# ptschematic.net
KiCad netlist of a schematic drawn in EAGLE
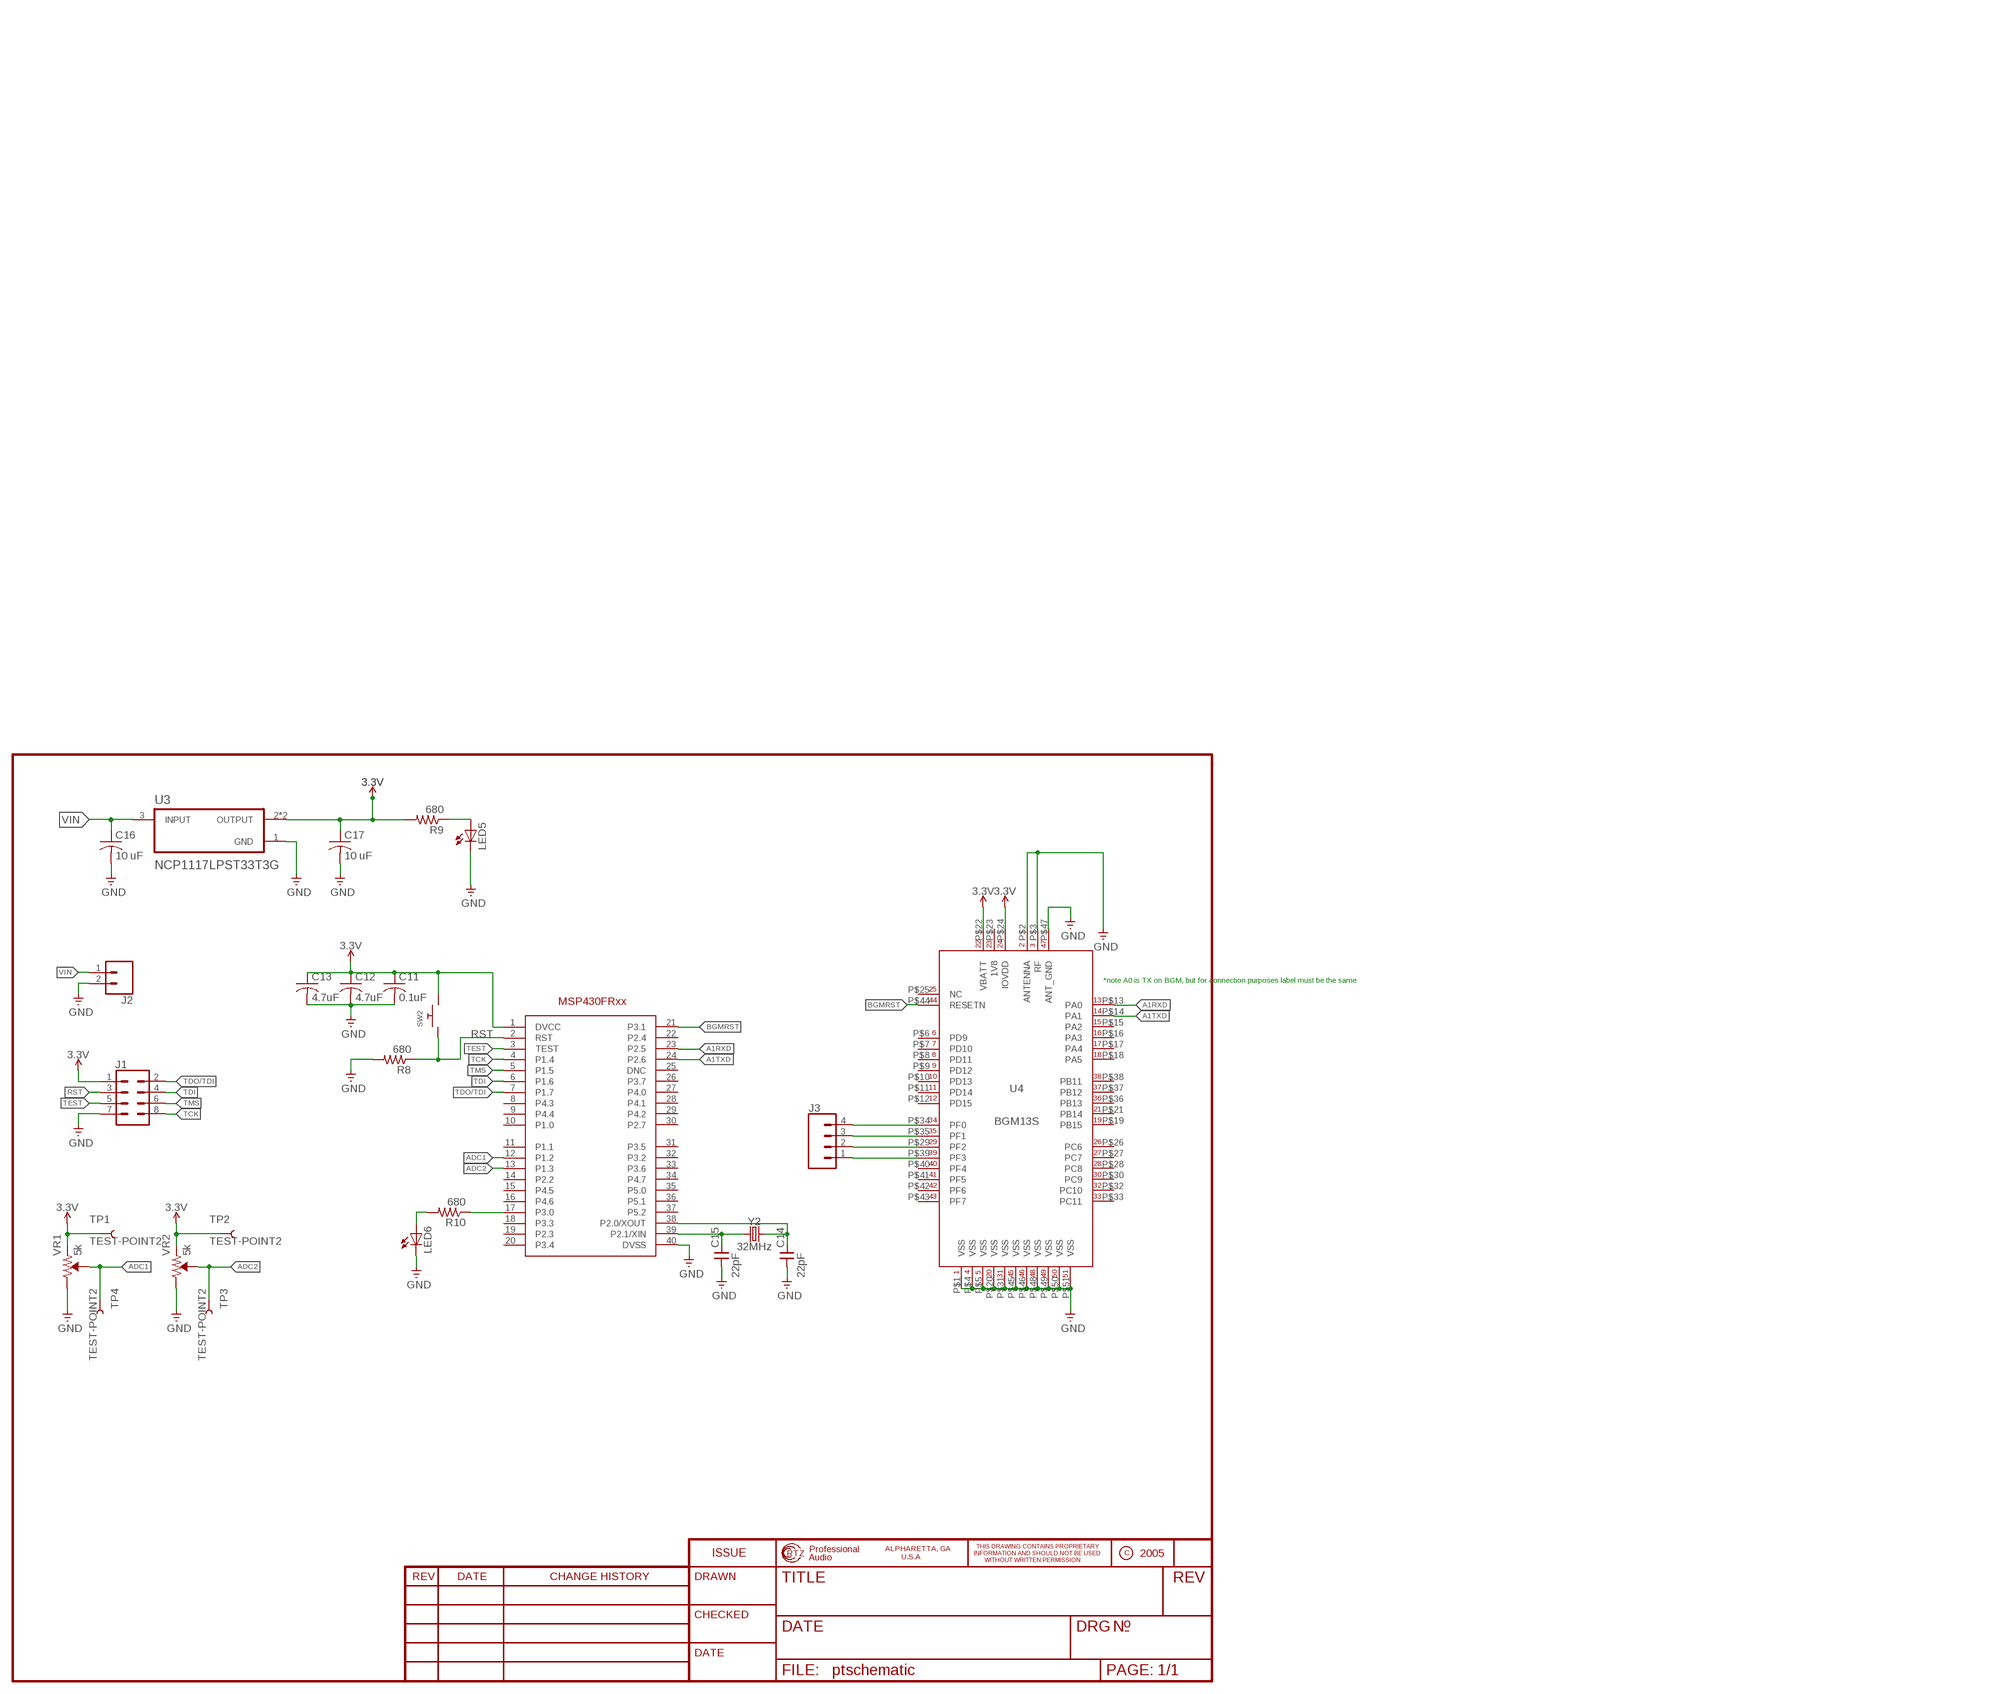
[diagram p0: schematic, sheet 1]

(export (version "E")
  (design (tool "Eeschema 10.0.6"))
  (components
    (comp (ref "C11")
      (value "0.1uF")
      (footprint "eagle-import:C0805")
      (libsource (lib "eagle-import") (part "C-USC0805"))
    )
    (comp (ref "C12")
      (value "4.7uF")
      (footprint "eagle-import:C0805")
      (libsource (lib "eagle-import") (part "C-USC0805"))
    )
    (comp (ref "C13")
      (value "4.7uF")
      (footprint "eagle-import:C0805")
      (libsource (lib "eagle-import") (part "C-USC0805"))
    )
    (comp (ref "C14")
      (value "22pF")
      (footprint "eagle-import:0805")
      (libsource (lib "eagle-import") (part "CNP-0805"))
    )
    (comp (ref "C15")
      (value "22pF")
      (footprint "eagle-import:0805")
      (libsource (lib "eagle-import") (part "CNP-0805"))
    )
    (comp (ref "C16")
      (value "10 uF")
      (footprint "eagle-import:C0805")
      (libsource (lib "eagle-import") (part "C-USC0805"))
    )
    (comp (ref "C17")
      (value "10 uF")
      (footprint "eagle-import:C0805")
      (libsource (lib "eagle-import") (part "C-USC0805"))
    )
    (comp (ref "J1")
      (value "CONN_04X2")
      (footprint "eagle-import:2X4")
      (libsource (lib "eagle-import") (part "CONN_04X2"))
    )
    (comp (ref "J2")
      (value "CONN_02")
      (footprint "eagle-import:1X02")
      (libsource (lib "eagle-import") (part "CONN_02"))
    )
    (comp (ref "J3")
      (value "CONN_04")
      (footprint "eagle-import:1X04")
      (libsource (lib "eagle-import") (part "CONN_04"))
    )
    (comp (ref "LED5")
      (value "LEDCHIPLED_0805")
      (footprint "eagle-import:CHIPLED_0805")
      (libsource (lib "eagle-import") (part "LEDCHIPLED_0805"))
    )
    (comp (ref "LED6")
      (value "LEDCHIPLED_0805")
      (footprint "eagle-import:CHIPLED_0805")
      (libsource (lib "eagle-import") (part "LEDCHIPLED_0805"))
    )
    (comp (ref "R8")
      (value "680")
      (footprint "eagle-import:R0805")
      (libsource (lib "eagle-import") (part "R-US_R0805"))
    )
    (comp (ref "R9")
      (value "680")
      (footprint "eagle-import:R0805")
      (libsource (lib "eagle-import") (part "R-US_R0805"))
    )
    (comp (ref "R10")
      (value "680")
      (footprint "eagle-import:R0805")
      (libsource (lib "eagle-import") (part "R-US_R0805"))
    )
    (comp (ref "SW2")
      (value "SWITCH_PUSHBUTTONEVQ-PE")
      (footprint "eagle-import:TACT_PANA-EVQ")
      (libsource (lib "eagle-import") (part "SWITCH_PUSHBUTTONEVQ-PE"))
    )
    (comp (ref "TP1")
      (value "TEST-POINT2")
      (footprint "eagle-import:PAD.02X.02")
      (libsource (lib "eagle-import") (part "TEST-POINT2"))
    )
    (comp (ref "TP2")
      (value "TEST-POINT2")
      (footprint "eagle-import:PAD.02X.02")
      (libsource (lib "eagle-import") (part "TEST-POINT2"))
    )
    (comp (ref "TP3")
      (value "TEST-POINT2")
      (footprint "eagle-import:PAD.02X.02")
      (libsource (lib "eagle-import") (part "TEST-POINT2"))
    )
    (comp (ref "TP4")
      (value "TEST-POINT2")
      (footprint "eagle-import:PAD.02X.02")
      (libsource (lib "eagle-import") (part "TEST-POINT2"))
    )
    (comp (ref "U$1")
      (value "MSP340FR247")
      (footprint "eagle-import:QFN-40")
      (libsource (lib "eagle-import") (part "MSP340FR247"))
    )
    (comp (ref "U3")
      (value "NCP1117LPST33T3G")
      (footprint "eagle-import:SOT230P700X175-4N")
      (fields (field (name "MF") "ON Semiconductor"))
      (libsource (lib "eagle-import") (part "NCP1117LPST33T3G"))
    )
    (comp (ref "U4")
      (value "BGM13S")
      (footprint "eagle-import:BGM13S")
      (libsource (lib "eagle-import") (part "BGM13S"))
    )
    (comp (ref "VR1")
      (value "5k")
      (footprint "eagle-import:TRIMPOT-SMD-5MM")
      (libsource (lib "eagle-import") (part "TRIMPOT-SMD-5MM-CLOSED-1/4W-20%"))
    )
    (comp (ref "VR2")
      (value "5k")
      (footprint "eagle-import:TRIMPOT-SMD-5MM")
      (libsource (lib "eagle-import") (part "TRIMPOT-SMD-5MM-CLOSED-1/4W-20%"))
    )
    (comp (ref "Y2")
      (value "32MHz")
      (footprint "eagle-import:CRYSTAL-SMD-2.0X1.6MM")
      (libsource (lib "eagle-import") (part "CRYSTAL-32MHZ-SMD-2.0X1.6MM"))
    )
  )
  (nets
    (net (code "1") (name "/1V8") (class "Default")
      (node (ref "U4") (pin "P$23") (pinfunction "1V8_P$23") (pintype "power_in"))
    )
    (net (code "2") (name "3.3V") (class "Default")
      (node (ref "C11") (pin "1") (pinfunction "1_1") (pintype "passive"))
      (node (ref "C12") (pin "1") (pinfunction "1_1") (pintype "passive"))
      (node (ref "C13") (pin "1") (pinfunction "1_1") (pintype "passive"))
      (node (ref "C17") (pin "1") (pinfunction "1_1") (pintype "passive"))
      (node (ref "J1") (pin "1") (pinfunction "1_1") (pintype "passive"))
      (node (ref "R9") (pin "2") (pinfunction "2_2") (pintype "passive"))
      (node (ref "SW2") (pin "P$2") (pinfunction "P$2_P$2") (pintype "passive"))
      (node (ref "TP1") (pin "P$1") (pinfunction "1_P$1") (pintype "bidirectional"))
      (node (ref "TP2") (pin "P$1") (pinfunction "1_P$1") (pintype "bidirectional"))
      (node (ref "U$1") (pin "1") (pinfunction "DVCC_1") (pintype "bidirectional"))
      (node (ref "U3") (pin "2") (pinfunction "OUTPUT_2") (pintype "output"))
      (node (ref "U3") (pin "4") (pinfunction "OUTPUT_4") (pintype "output"))
      (node (ref "U4") (pin "P$22") (pinfunction "VBATT_P$22") (pintype "power_in"))
      (node (ref "U4") (pin "P$24") (pinfunction "IOVDD_P$24") (pintype "power_in"))
      (node (ref "VR1") (pin "A") (pinfunction "CCW_A") (pintype "passive"))
      (node (ref "VR2") (pin "A") (pinfunction "CCW_A") (pintype "passive"))
    )
    (net (code "3") (name "A1RXD") (class "Default")
      (node (ref "U$1") (pin "23") (pinfunction "P2.5_23") (pintype "bidirectional"))
      (node (ref "U4") (pin "P$13") (pinfunction "PA0_P$13") (pintype "bidirectional"))
    )
    (net (code "4") (name "A1TXD") (class "Default")
      (node (ref "U$1") (pin "24") (pinfunction "P2.6_24") (pintype "bidirectional"))
      (node (ref "U4") (pin "P$14") (pinfunction "PA1_P$14") (pintype "bidirectional"))
    )
    (net (code "5") (name "ADC1") (class "Default")
      (node (ref "TP4") (pin "P$1") (pinfunction "1_P$1") (pintype "bidirectional"))
      (node (ref "U$1") (pin "12") (pinfunction "P1.2_12") (pintype "bidirectional"))
      (node (ref "VR1") (pin "B") (pinfunction "WIPER_B") (pintype "passive"))
    )
    (net (code "6") (name "ADC2") (class "Default")
      (node (ref "TP3") (pin "P$1") (pinfunction "1_P$1") (pintype "bidirectional"))
      (node (ref "U$1") (pin "13") (pinfunction "P1.3_13") (pintype "bidirectional"))
      (node (ref "VR2") (pin "B") (pinfunction "WIPER_B") (pintype "passive"))
    )
    (net (code "7") (name "BGMRST") (class "Default")
      (node (ref "U$1") (pin "21") (pinfunction "P3.1_21") (pintype "bidirectional"))
      (node (ref "U4") (pin "P$44") (pinfunction "RESETN_P$44") (pintype "bidirectional"))
    )
    (net (code "8") (name "GND") (class "Default")
      (node (ref "C11") (pin "2") (pinfunction "2_2") (pintype "passive"))
      (node (ref "C12") (pin "2") (pinfunction "2_2") (pintype "passive"))
      (node (ref "C13") (pin "2") (pinfunction "2_2") (pintype "passive"))
      (node (ref "C14") (pin "1") (pinfunction "1_1") (pintype "passive"))
      (node (ref "C15") (pin "1") (pinfunction "1_1") (pintype "passive"))
      (node (ref "C16") (pin "2") (pinfunction "2_2") (pintype "passive"))
      (node (ref "C17") (pin "2") (pinfunction "2_2") (pintype "passive"))
      (node (ref "J1") (pin "7") (pinfunction "7_7") (pintype "passive"))
      (node (ref "J2") (pin "2") (pinfunction "2_2") (pintype "passive"))
      (node (ref "LED5") (pin "C") (pinfunction "C_C") (pintype "passive"))
      (node (ref "LED6") (pin "C") (pinfunction "C_C") (pintype "passive"))
      (node (ref "R8") (pin "2") (pinfunction "2_2") (pintype "passive"))
      (node (ref "U$1") (pin "40") (pinfunction "DVSS_40") (pintype "bidirectional"))
      (node (ref "U3") (pin "1") (pinfunction "GND_1") (pintype "power_in"))
      (node (ref "U4") (pin "P$1") (pinfunction "VSS_P$1") (pintype "power_in"))
      (node (ref "U4") (pin "P$2") (pinfunction "ANTENNA_P$2") (pintype "passive"))
      (node (ref "U4") (pin "P$20") (pinfunction "VSS_P$20") (pintype "power_in"))
      (node (ref "U4") (pin "P$3") (pinfunction "RF_P$3") (pintype "passive"))
      (node (ref "U4") (pin "P$31") (pinfunction "VSS_P$31") (pintype "power_in"))
      (node (ref "U4") (pin "P$4") (pinfunction "VSS_P$4") (pintype "power_in"))
      (node (ref "U4") (pin "P$45") (pinfunction "VSS_P$45") (pintype "power_in"))
      (node (ref "U4") (pin "P$46") (pinfunction "VSS_P$46") (pintype "power_in"))
      (node (ref "U4") (pin "P$47") (pinfunction "ANT_GND_P$47") (pintype "power_in"))
      (node (ref "U4") (pin "P$48") (pinfunction "VSS_P$48") (pintype "power_in"))
      (node (ref "U4") (pin "P$49") (pinfunction "VSS_P$49") (pintype "power_in"))
      (node (ref "U4") (pin "P$5") (pinfunction "VSS_P$5") (pintype "power_in"))
      (node (ref "U4") (pin "P$50") (pinfunction "VSS_P$50") (pintype "power_in"))
      (node (ref "U4") (pin "P$51") (pinfunction "VSS_P$51") (pintype "power_in"))
      (node (ref "VR1") (pin "C") (pinfunction "CW_C") (pintype "passive"))
      (node (ref "VR2") (pin "C") (pinfunction "CW_C") (pintype "passive"))
    )
    (net (code "9") (name "Net-(LED5-PadA)") (class "Default")
      (node (ref "LED5") (pin "A") (pinfunction "A_A") (pintype "passive"))
      (node (ref "R9") (pin "1") (pinfunction "1_1") (pintype "passive"))
    )
    (net (code "10") (name "Net-(LED6-PadA)") (class "Default")
      (node (ref "LED6") (pin "A") (pinfunction "A_A") (pintype "passive"))
      (node (ref "R10") (pin "2") (pinfunction "2_2") (pintype "passive"))
    )
    (net (code "11") (name "Net-(U$1-P2.0{slash}XOUT)") (class "Default")
      (node (ref "C14") (pin "2") (pinfunction "2_2") (pintype "passive"))
      (node (ref "U$1") (pin "38") (pinfunction "P2.0/XOUT_38") (pintype "bidirectional"))
      (node (ref "Y2") (pin "3") (pinfunction "2_3") (pintype "passive"))
    )
    (net (code "12") (name "Net-(U$1-P2.1{slash}XIN)") (class "Default")
      (node (ref "C15") (pin "2") (pinfunction "2_2") (pintype "passive"))
      (node (ref "U$1") (pin "39") (pinfunction "P2.1/XIN_39") (pintype "bidirectional"))
      (node (ref "Y2") (pin "1") (pinfunction "1_1") (pintype "passive"))
    )
    (net (code "13") (name "Net-(U$1-P3.0)") (class "Default")
      (node (ref "R10") (pin "1") (pinfunction "1_1") (pintype "passive"))
      (node (ref "U$1") (pin "17") (pinfunction "P3.0_17") (pintype "bidirectional"))
    )
    (net (code "14") (name "Net-(U4-PF0)") (class "Default")
      (node (ref "J3") (pin "4") (pinfunction "4_4") (pintype "passive"))
      (node (ref "U4") (pin "P$34") (pinfunction "PF0_P$34") (pintype "bidirectional"))
    )
    (net (code "15") (name "Net-(U4-PF1)") (class "Default")
      (node (ref "J3") (pin "3") (pinfunction "3_3") (pintype "passive"))
      (node (ref "U4") (pin "P$35") (pinfunction "PF1_P$35") (pintype "bidirectional"))
    )
    (net (code "16") (name "Net-(U4-PF2)") (class "Default")
      (node (ref "J3") (pin "2") (pinfunction "2_2") (pintype "passive"))
      (node (ref "U4") (pin "P$29") (pinfunction "PF2_P$29") (pintype "bidirectional"))
    )
    (net (code "17") (name "Net-(U4-PF3)") (class "Default")
      (node (ref "J3") (pin "1") (pinfunction "1_1") (pintype "passive"))
      (node (ref "U4") (pin "P$39") (pinfunction "PF3_P$39") (pintype "bidirectional"))
    )
    (net (code "18") (name "RST") (class "Default")
      (node (ref "J1") (pin "3") (pinfunction "3_3") (pintype "passive"))
      (node (ref "R8") (pin "1") (pinfunction "1_1") (pintype "passive"))
      (node (ref "SW2") (pin "P$1") (pinfunction "P$1_P$1") (pintype "passive"))
      (node (ref "U$1") (pin "2") (pinfunction "RST_2") (pintype "bidirectional"))
    )
    (net (code "19") (name "TCK") (class "Default")
      (node (ref "J1") (pin "8") (pinfunction "8_8") (pintype "passive"))
      (node (ref "U$1") (pin "4") (pinfunction "P1.4_4") (pintype "bidirectional"))
    )
    (net (code "20") (name "TDI") (class "Default")
      (node (ref "J1") (pin "4") (pinfunction "4_4") (pintype "passive"))
      (node (ref "U$1") (pin "6") (pinfunction "P1.6_6") (pintype "bidirectional"))
    )
    (net (code "21") (name "TDO{slash}TDI") (class "Default")
      (node (ref "J1") (pin "2") (pinfunction "2_2") (pintype "passive"))
      (node (ref "U$1") (pin "7") (pinfunction "P1.7_7") (pintype "bidirectional"))
    )
    (net (code "22") (name "TEST") (class "Default")
      (node (ref "J1") (pin "5") (pinfunction "5_5") (pintype "passive"))
      (node (ref "U$1") (pin "3") (pinfunction "TEST_3") (pintype "bidirectional"))
    )
    (net (code "23") (name "TMS") (class "Default")
      (node (ref "J1") (pin "6") (pinfunction "6_6") (pintype "passive"))
      (node (ref "U$1") (pin "5") (pinfunction "P1.5_5") (pintype "bidirectional"))
    )
    (net (code "24") (name "VIN") (class "Default")
      (node (ref "C16") (pin "1") (pinfunction "1_1") (pintype "passive"))
      (node (ref "J2") (pin "1") (pinfunction "1_1") (pintype "passive"))
      (node (ref "U3") (pin "3") (pinfunction "INPUT_3") (pintype "input"))
    )
    (net (code "25") (name "unconnected-(U$1-DNC-Pad25)") (class "Default")
      (node (ref "U$1") (pin "25") (pinfunction "DNC_25") (pintype "bidirectional"))
    )
    (net (code "26") (name "unconnected-(U$1-P1.0-Pad10)") (class "Default")
      (node (ref "U$1") (pin "10") (pinfunction "P1.0_10") (pintype "bidirectional"))
    )
    (net (code "27") (name "unconnected-(U$1-P1.1-Pad11)") (class "Default")
      (node (ref "U$1") (pin "11") (pinfunction "P1.1_11") (pintype "bidirectional"))
    )
    (net (code "28") (name "unconnected-(U$1-P2.2-Pad14)") (class "Default")
      (node (ref "U$1") (pin "14") (pinfunction "P2.2_14") (pintype "bidirectional"))
    )
    (net (code "29") (name "unconnected-(U$1-P2.3-Pad19)") (class "Default")
      (node (ref "U$1") (pin "19") (pinfunction "P2.3_19") (pintype "bidirectional"))
    )
    (net (code "30") (name "unconnected-(U$1-P2.4-Pad22)") (class "Default")
      (node (ref "U$1") (pin "22") (pinfunction "P2.4_22") (pintype "bidirectional"))
    )
    (net (code "31") (name "unconnected-(U$1-P2.7-Pad30)") (class "Default")
      (node (ref "U$1") (pin "30") (pinfunction "P2.7_30") (pintype "bidirectional"))
    )
    (net (code "32") (name "unconnected-(U$1-P3.2-Pad32)") (class "Default")
      (node (ref "U$1") (pin "32") (pinfunction "P3.2_32") (pintype "bidirectional"))
    )
    (net (code "33") (name "unconnected-(U$1-P3.3-Pad18)") (class "Default")
      (node (ref "U$1") (pin "18") (pinfunction "P3.3_18") (pintype "bidirectional"))
    )
    (net (code "34") (name "unconnected-(U$1-P3.4-Pad20)") (class "Default")
      (node (ref "U$1") (pin "20") (pinfunction "P3.4_20") (pintype "bidirectional"))
    )
    (net (code "35") (name "unconnected-(U$1-P3.5-Pad31)") (class "Default")
      (node (ref "U$1") (pin "31") (pinfunction "P3.5_31") (pintype "bidirectional"))
    )
    (net (code "36") (name "unconnected-(U$1-P3.6-Pad33)") (class "Default")
      (node (ref "U$1") (pin "33") (pinfunction "P3.6_33") (pintype "bidirectional"))
    )
    (net (code "37") (name "unconnected-(U$1-P3.7-Pad26)") (class "Default")
      (node (ref "U$1") (pin "26") (pinfunction "P3.7_26") (pintype "bidirectional"))
    )
    (net (code "38") (name "unconnected-(U$1-P4.0-Pad27)") (class "Default")
      (node (ref "U$1") (pin "27") (pinfunction "P4.0_27") (pintype "bidirectional"))
    )
    (net (code "39") (name "unconnected-(U$1-P4.1-Pad28)") (class "Default")
      (node (ref "U$1") (pin "28") (pinfunction "P4.1_28") (pintype "bidirectional"))
    )
    (net (code "40") (name "unconnected-(U$1-P4.2-Pad29)") (class "Default")
      (node (ref "U$1") (pin "29") (pinfunction "P4.2_29") (pintype "bidirectional"))
    )
    (net (code "41") (name "unconnected-(U$1-P4.3-Pad8)") (class "Default")
      (node (ref "U$1") (pin "8") (pinfunction "P4.3_8") (pintype "bidirectional"))
    )
    (net (code "42") (name "unconnected-(U$1-P4.4-Pad9)") (class "Default")
      (node (ref "U$1") (pin "9") (pinfunction "P4.4_9") (pintype "bidirectional"))
    )
    (net (code "43") (name "unconnected-(U$1-P4.5-Pad15)") (class "Default")
      (node (ref "U$1") (pin "15") (pinfunction "P4.5_15") (pintype "bidirectional"))
    )
    (net (code "44") (name "unconnected-(U$1-P4.6-Pad16)") (class "Default")
      (node (ref "U$1") (pin "16") (pinfunction "P4.6_16") (pintype "bidirectional"))
    )
    (net (code "45") (name "unconnected-(U$1-P4.7-Pad34)") (class "Default")
      (node (ref "U$1") (pin "34") (pinfunction "P4.7_34") (pintype "bidirectional"))
    )
    (net (code "46") (name "unconnected-(U$1-P5.0-Pad35)") (class "Default")
      (node (ref "U$1") (pin "35") (pinfunction "P5.0_35") (pintype "bidirectional"))
    )
    (net (code "47") (name "unconnected-(U$1-P5.1-Pad36)") (class "Default")
      (node (ref "U$1") (pin "36") (pinfunction "P5.1_36") (pintype "bidirectional"))
    )
    (net (code "48") (name "unconnected-(U$1-P5.2-Pad37)") (class "Default")
      (node (ref "U$1") (pin "37") (pinfunction "P5.2_37") (pintype "bidirectional"))
    )
    (net (code "49") (name "unconnected-(U4-NC-PadP$25)") (class "Default")
      (node (ref "U4") (pin "P$25") (pinfunction "NC_P$25") (pintype "no_connect"))
    )
    (net (code "50") (name "unconnected-(U4-PA2-PadP$15)") (class "Default")
      (node (ref "U4") (pin "P$15") (pinfunction "PA2_P$15") (pintype "bidirectional"))
    )
    (net (code "51") (name "unconnected-(U4-PA3-PadP$16)") (class "Default")
      (node (ref "U4") (pin "P$16") (pinfunction "PA3_P$16") (pintype "bidirectional"))
    )
    (net (code "52") (name "unconnected-(U4-PA4-PadP$17)") (class "Default")
      (node (ref "U4") (pin "P$17") (pinfunction "PA4_P$17") (pintype "bidirectional"))
    )
    (net (code "53") (name "unconnected-(U4-PA5-PadP$18)") (class "Default")
      (node (ref "U4") (pin "P$18") (pinfunction "PA5_P$18") (pintype "bidirectional"))
    )
    (net (code "54") (name "unconnected-(U4-PB11-PadP$38)") (class "Default")
      (node (ref "U4") (pin "P$38") (pinfunction "PB11_P$38") (pintype "bidirectional"))
    )
    (net (code "55") (name "unconnected-(U4-PB12-PadP$37)") (class "Default")
      (node (ref "U4") (pin "P$37") (pinfunction "PB12_P$37") (pintype "bidirectional"))
    )
    (net (code "56") (name "unconnected-(U4-PB13-PadP$36)") (class "Default")
      (node (ref "U4") (pin "P$36") (pinfunction "PB13_P$36") (pintype "bidirectional"))
    )
    (net (code "57") (name "unconnected-(U4-PB14-PadP$21)") (class "Default")
      (node (ref "U4") (pin "P$21") (pinfunction "PB14_P$21") (pintype "bidirectional"))
    )
    (net (code "58") (name "unconnected-(U4-PB15-PadP$19)") (class "Default")
      (node (ref "U4") (pin "P$19") (pinfunction "PB15_P$19") (pintype "bidirectional"))
    )
    (net (code "59") (name "unconnected-(U4-PC6-PadP$26)") (class "Default")
      (node (ref "U4") (pin "P$26") (pinfunction "PC6_P$26") (pintype "bidirectional"))
    )
    (net (code "60") (name "unconnected-(U4-PC7-PadP$27)") (class "Default")
      (node (ref "U4") (pin "P$27") (pinfunction "PC7_P$27") (pintype "bidirectional"))
    )
    (net (code "61") (name "unconnected-(U4-PC8-PadP$28)") (class "Default")
      (node (ref "U4") (pin "P$28") (pinfunction "PC8_P$28") (pintype "bidirectional"))
    )
    (net (code "62") (name "unconnected-(U4-PC9-PadP$30)") (class "Default")
      (node (ref "U4") (pin "P$30") (pinfunction "PC9_P$30") (pintype "bidirectional"))
    )
    (net (code "63") (name "unconnected-(U4-PC10-PadP$32)") (class "Default")
      (node (ref "U4") (pin "P$32") (pinfunction "PC10_P$32") (pintype "bidirectional"))
    )
    (net (code "64") (name "unconnected-(U4-PC11-PadP$33)") (class "Default")
      (node (ref "U4") (pin "P$33") (pinfunction "PC11_P$33") (pintype "bidirectional"))
    )
    (net (code "65") (name "unconnected-(U4-PD9-PadP$6)") (class "Default")
      (node (ref "U4") (pin "P$6") (pinfunction "PD9_P$6") (pintype "bidirectional"))
    )
    (net (code "66") (name "unconnected-(U4-PD10-PadP$7)") (class "Default")
      (node (ref "U4") (pin "P$7") (pinfunction "PD10_P$7") (pintype "bidirectional"))
    )
    (net (code "67") (name "unconnected-(U4-PD11-PadP$8)") (class "Default")
      (node (ref "U4") (pin "P$8") (pinfunction "PD11_P$8") (pintype "bidirectional"))
    )
    (net (code "68") (name "unconnected-(U4-PD12-PadP$9)") (class "Default")
      (node (ref "U4") (pin "P$9") (pinfunction "PD12_P$9") (pintype "bidirectional"))
    )
    (net (code "69") (name "unconnected-(U4-PD13-PadP$10)") (class "Default")
      (node (ref "U4") (pin "P$10") (pinfunction "PD13_P$10") (pintype "bidirectional"))
    )
    (net (code "70") (name "unconnected-(U4-PD14-PadP$11)") (class "Default")
      (node (ref "U4") (pin "P$11") (pinfunction "PD14_P$11") (pintype "bidirectional"))
    )
    (net (code "71") (name "unconnected-(U4-PD15-PadP$12)") (class "Default")
      (node (ref "U4") (pin "P$12") (pinfunction "PD15_P$12") (pintype "bidirectional"))
    )
    (net (code "72") (name "unconnected-(U4-PF4-PadP$40)") (class "Default")
      (node (ref "U4") (pin "P$40") (pinfunction "PF4_P$40") (pintype "bidirectional"))
    )
    (net (code "73") (name "unconnected-(U4-PF5-PadP$41)") (class "Default")
      (node (ref "U4") (pin "P$41") (pinfunction "PF5_P$41") (pintype "bidirectional"))
    )
    (net (code "74") (name "unconnected-(U4-PF6-PadP$42)") (class "Default")
      (node (ref "U4") (pin "P$42") (pinfunction "PF6_P$42") (pintype "bidirectional"))
    )
    (net (code "75") (name "unconnected-(U4-PF7-PadP$43)") (class "Default")
      (node (ref "U4") (pin "P$43") (pinfunction "PF7_P$43") (pintype "bidirectional"))
    )
  )
)
